# USB.net
KiCad netlist of a schematic drawn in Altium Designer
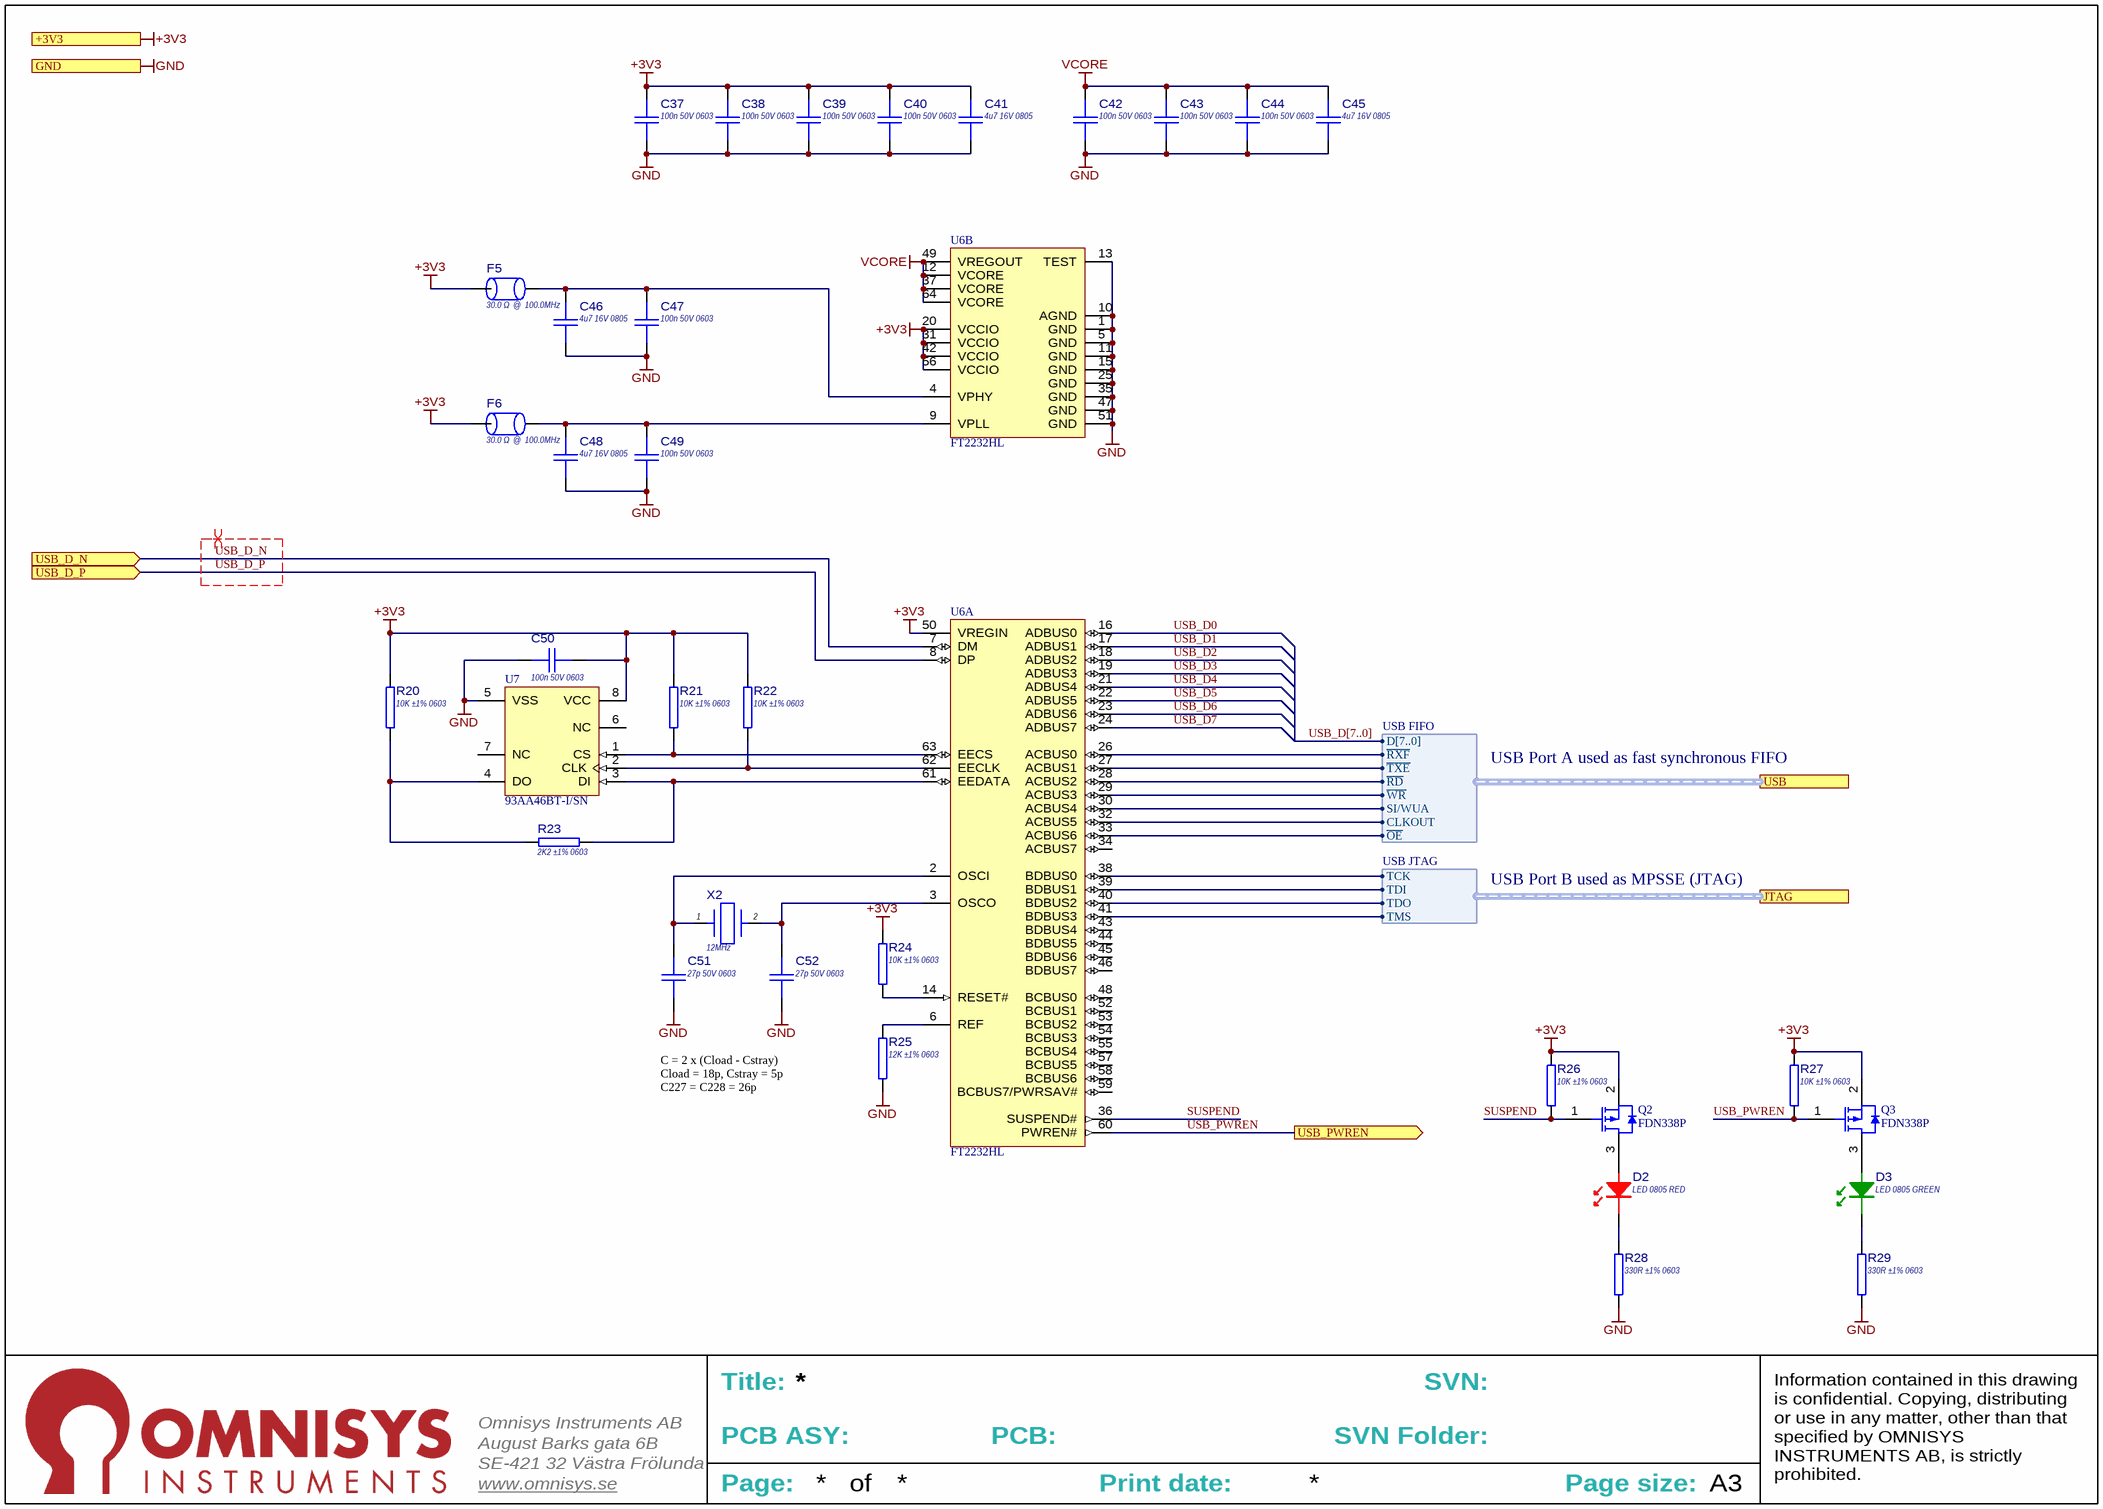
[diagram p0: USB.SchDoc]

(export (version "E")
  (design (tool "Eeschema 10.0.6"))
  (components
    (comp (ref "C37")
      (value "100n 50V 0603")
      (footprint "CAPC1608X90N")
      (description "100n 50V X7R ±10% 0603 (1608 metric)")
      (fields (field (name "PARTNUMBER") "GRM188R71H104KA93") (field (name "TOLERANCE") "±10%"))
      (libsource (lib "Omnisys Vault") (part "CAP-2PIN"))
    )
    (comp (ref "C38")
      (value "100n 50V 0603")
      (footprint "CAPC1608X90N")
      (description "100n 50V X7R ±10% 0603 (1608 metric)")
      (fields (field (name "PARTNUMBER") "GRM188R71H104KA93") (field (name "TOLERANCE") "±10%"))
      (libsource (lib "Omnisys Vault") (part "CAP-2PIN"))
    )
    (comp (ref "C39")
      (value "100n 50V 0603")
      (footprint "CAPC1608X90N")
      (description "100n 50V X7R ±10% 0603 (1608 metric)")
      (fields (field (name "PARTNUMBER") "GRM188R71H104KA93") (field (name "TOLERANCE") "±10%"))
      (libsource (lib "Omnisys Vault") (part "CAP-2PIN"))
    )
    (comp (ref "C40")
      (value "100n 50V 0603")
      (footprint "CAPC1608X90N")
      (description "100n 50V X7R ±10% 0603 (1608 metric)")
      (fields (field (name "PARTNUMBER") "GRM188R71H104KA93") (field (name "TOLERANCE") "±10%"))
      (libsource (lib "Omnisys Vault") (part "CAP-2PIN"))
    )
    (comp (ref "C41")
      (value "4u7 16V 0805")
      (footprint "CAPC2012X140N")
      (description "4u7 16V X7R ±10% 0805 (2012 metric)")
      (fields (field (name "PARTNUMBER") "GRM21BR71C475KA73") (field (name "TOLERANCE") "10%"))
      (libsource (lib "Omnisys Vault") (part "CAP-2PIN"))
    )
    (comp (ref "C42")
      (value "100n 50V 0603")
      (footprint "CAPC1608X90N")
      (description "100n 50V X7R ±10% 0603 (1608 metric)")
      (fields (field (name "PARTNUMBER") "GRM188R71H104KA93") (field (name "TOLERANCE") "±10%"))
      (libsource (lib "Omnisys Vault") (part "CAP-2PIN"))
    )
    (comp (ref "C43")
      (value "100n 50V 0603")
      (footprint "CAPC1608X90N")
      (description "100n 50V X7R ±10% 0603 (1608 metric)")
      (fields (field (name "PARTNUMBER") "GRM188R71H104KA93") (field (name "TOLERANCE") "±10%"))
      (libsource (lib "Omnisys Vault") (part "CAP-2PIN"))
    )
    (comp (ref "C44")
      (value "100n 50V 0603")
      (footprint "CAPC1608X90N")
      (description "100n 50V X7R ±10% 0603 (1608 metric)")
      (fields (field (name "PARTNUMBER") "GRM188R71H104KA93") (field (name "TOLERANCE") "±10%"))
      (libsource (lib "Omnisys Vault") (part "CAP-2PIN"))
    )
    (comp (ref "C45")
      (value "4u7 16V 0805")
      (footprint "CAPC2012X140N")
      (description "4u7 16V X7R ±10% 0805 (2012 metric)")
      (fields (field (name "PARTNUMBER") "GRM21BR71C475KA73") (field (name "TOLERANCE") "10%"))
      (libsource (lib "Omnisys Vault") (part "CAP-2PIN"))
    )
    (comp (ref "C46")
      (value "4u7 16V 0805")
      (footprint "CAPC2012X140N")
      (description "4u7 16V X7R ±10% 0805 (2012 metric)")
      (fields (field (name "PARTNUMBER") "GRM21BR71C475KA73") (field (name "TOLERANCE") "10%"))
      (libsource (lib "Omnisys Vault") (part "CAP-2PIN"))
    )
    (comp (ref "C47")
      (value "100n 50V 0603")
      (footprint "CAPC1608X90N")
      (description "100n 50V X7R ±10% 0603 (1608 metric)")
      (fields (field (name "PARTNUMBER") "GRM188R71H104KA93") (field (name "TOLERANCE") "±10%"))
      (libsource (lib "Omnisys Vault") (part "CAP-2PIN"))
    )
    (comp (ref "C48")
      (value "4u7 16V 0805")
      (footprint "CAPC2012X140N")
      (description "4u7 16V X7R ±10% 0805 (2012 metric)")
      (fields (field (name "PARTNUMBER") "GRM21BR71C475KA73") (field (name "TOLERANCE") "10%"))
      (libsource (lib "Omnisys Vault") (part "CAP-2PIN"))
    )
    (comp (ref "C49")
      (value "100n 50V 0603")
      (footprint "CAPC1608X90N")
      (description "100n 50V X7R ±10% 0603 (1608 metric)")
      (fields (field (name "PARTNUMBER") "GRM188R71H104KA93") (field (name "TOLERANCE") "±10%"))
      (libsource (lib "Omnisys Vault") (part "CAP-2PIN"))
    )
    (comp (ref "C50")
      (value "100n 50V 0603")
      (footprint "CAPC1608X90N")
      (description "100n 50V X7R ±10% 0603 (1608 metric)")
      (fields (field (name "PARTNUMBER") "GRM188R71H104KA93") (field (name "TOLERANCE") "±10%"))
      (libsource (lib "Omnisys Vault") (part "CAP-2PIN"))
    )
    (comp (ref "C51")
      (value "27p 50V 0603")
      (footprint "CAPC1608X90N")
      (description "27p 50V C0G ±5% 0603 (1608 metric)")
      (fields (field (name "PARTNUMBER") "GRM1885C1H270JA01") (field (name "TOLERANCE") "±5%"))
      (libsource (lib "Omnisys Vault") (part "CAP-2PIN"))
    )
    (comp (ref "C52")
      (value "27p 50V 0603")
      (footprint "CAPC1608X90N")
      (description "27p 50V C0G ±5% 0603 (1608 metric)")
      (fields (field (name "PARTNUMBER") "GRM1885C1H270JA01") (field (name "TOLERANCE") "±5%"))
      (libsource (lib "Omnisys Vault") (part "CAP-2PIN"))
    )
    (comp (ref "D2")
      (value "LED 0805 RED")
      (footprint "LED2012-RED")
      (libsource (lib "Omnisys Vault") (part "LED-2PIN-RED"))
    )
    (comp (ref "D3")
      (value "LED 0805 GREEN")
      (footprint "LED2012-GREEN")
      (libsource (lib "Omnisys Vault") (part "LED-2PIN-GREEN"))
    )
    (comp (ref "F5")
      (value "30.0 Ω  @  100.0MHz")
      (footprint "INDC2012X11N")
      (description "Ferrite bead, Würth Elektronik WE-CBF 2012 (0805), 74279206 ,  30.0 Ω  @  100.0MHz")
      (fields (field (name "PARTNUMBER") "74279206"))
      (libsource (lib "Omnisys Vault") (part "BEAD-2PIN"))
    )
    (comp (ref "F6")
      (value "30.0 Ω  @  100.0MHz")
      (footprint "INDC2012X11N")
      (description "Ferrite bead, Würth Elektronik WE-CBF 2012 (0805), 74279206 ,  30.0 Ω  @  100.0MHz")
      (fields (field (name "PARTNUMBER") "74279206"))
      (libsource (lib "Omnisys Vault") (part "BEAD-2PIN"))
    )
    (comp (ref "Q2")
      (value "FDN338P")
      (footprint "FAIR-SSOT3L-3_V")
      (fields (field (name "MANUFACTURER") "Fairchild Semiconductor"))
      (libsource (lib "Altium Content Vault") (part "PEMOS-GSD-3"))
    )
    (comp (ref "Q3")
      (value "FDN338P")
      (footprint "FAIR-SSOT3L-3_V")
      (fields (field (name "MANUFACTURER") "Fairchild Semiconductor"))
      (libsource (lib "Altium Content Vault") (part "PEMOS-GSD-3"))
    )
    (comp (ref "R20")
      (value "10K ±1% 0603")
      (footprint "RESC1608N")
      (description "10K ±1% ±100 ppm/˚C 0.10W 75V 0603 (1608 metric)")
      (fields (field (name "POWER") "100mW") (field (name "TOLERANCE") "1%"))
      (libsource (lib "Omnisys Vault") (part "RES-2PIN"))
    )
    (comp (ref "R21")
      (value "10K ±1% 0603")
      (footprint "RESC1608N")
      (description "10K ±1% ±100 ppm/˚C 0.10W 75V 0603 (1608 metric)")
      (fields (field (name "POWER") "100mW") (field (name "TOLERANCE") "1%"))
      (libsource (lib "Omnisys Vault") (part "RES-2PIN"))
    )
    (comp (ref "R22")
      (value "10K ±1% 0603")
      (footprint "RESC1608N")
      (description "10K ±1% ±100 ppm/˚C 0.10W 75V 0603 (1608 metric)")
      (fields (field (name "POWER") "100mW") (field (name "TOLERANCE") "1%"))
      (libsource (lib "Omnisys Vault") (part "RES-2PIN"))
    )
    (comp (ref "R23")
      (value "2K2 ±1% 0603")
      (footprint "RESC1608N")
      (description "2K2 ±1% ±100 ppm/˚C 0.10W 75V 0603 (1608 metric)")
      (fields (field (name "POWER") "100mW") (field (name "TOLERANCE") "1%"))
      (libsource (lib "Omnisys Vault") (part "RES-2PIN"))
    )
    (comp (ref "R24")
      (value "10K ±1% 0603")
      (footprint "RESC1608N")
      (description "10K ±1% ±100 ppm/˚C 0.10W 75V 0603 (1608 metric)")
      (fields (field (name "POWER") "100mW") (field (name "TOLERANCE") "1%"))
      (libsource (lib "Omnisys Vault") (part "RES-2PIN"))
    )
    (comp (ref "R25")
      (value "12K ±1% 0603")
      (footprint "RESC1608N")
      (description "12K ±1% ±100 ppm/˚C 0.10W 75V 0603 (1608 metric)")
      (fields (field (name "POWER") "100mW") (field (name "TOLERANCE") "1%"))
      (libsource (lib "Omnisys Vault") (part "RES-2PIN"))
    )
    (comp (ref "R26")
      (value "10K ±1% 0603")
      (footprint "RESC1608N")
      (description "10K ±1% ±100 ppm/˚C 0.10W 75V 0603 (1608 metric)")
      (fields (field (name "POWER") "100mW") (field (name "TOLERANCE") "1%"))
      (libsource (lib "Omnisys Vault") (part "RES-2PIN"))
    )
    (comp (ref "R27")
      (value "10K ±1% 0603")
      (footprint "RESC1608N")
      (description "10K ±1% ±100 ppm/˚C 0.10W 75V 0603 (1608 metric)")
      (fields (field (name "POWER") "100mW") (field (name "TOLERANCE") "1%"))
      (libsource (lib "Omnisys Vault") (part "RES-2PIN"))
    )
    (comp (ref "R28")
      (value "330R ±1% 0603")
      (footprint "RESC1608N")
      (description "330R ±1% ±100 ppm/˚C 0.10W 75V 0603 (1608 metric)")
      (fields (field (name "POWER") "100mW") (field (name "TOLERANCE") "1%"))
      (libsource (lib "Omnisys Vault") (part "RES-2PIN"))
    )
    (comp (ref "R29")
      (value "330R ±1% 0603")
      (footprint "RESC1608N")
      (description "330R ±1% ±100 ppm/˚C 0.10W 75V 0603 (1608 metric)")
      (fields (field (name "POWER") "100mW") (field (name "TOLERANCE") "1%"))
      (libsource (lib "Omnisys Vault") (part "RES-2PIN"))
    )
    (comp (ref "U6")
      (value "FT2232HL")
      (footprint "FTDI-LQFP-64_L")
      (fields (field (name "MANUFACTURER") "FTDI"))
      (libsource (lib "Altium Content Vault") (part "FTDI-FT2232HL-LQFP-64"))
    )
    (comp (ref "U7")
      (value "93AA46BT-I/SN")
      (footprint "SOIC-SN8_L")
      (libsource (lib "Altium Content Vault") (part "MEM-SEEPROM-93AA46B-P-8"))
    )
    (comp (ref "X2")
      (value "12MHz")
      (footprint "XTAL_5x3.2MM")
      (description "12MHz 5 x 3.2 mm SMD GLASS CRYSTAL, 7A-12.000MAAJ-T")
      (fields (field (name "PARTNUMBER") "7A-12.000MAAJ-T"))
      (libsource (lib "Omnisys Vault") (part "XTAL-2PIN"))
    )
  )
  (nets
    (net (code "4") (name "+3V3") (class "Default")
      (node (ref "C37") (pin "1") (pinfunction "1_1") (pintype "passive"))
      (node (ref "C38") (pin "1") (pinfunction "1_1") (pintype "passive"))
      (node (ref "C39") (pin "1") (pinfunction "1_1") (pintype "passive"))
      (node (ref "C40") (pin "1") (pinfunction "1_1") (pintype "passive"))
      (node (ref "C41") (pin "2") (pinfunction "2_2") (pintype "passive"))
      (node (ref "C50") (pin "2") (pinfunction "2_2") (pintype "passive"))
      (node (ref "F5") (pin "1") (pinfunction "1_1") (pintype "passive"))
      (node (ref "F6") (pin "1") (pinfunction "1_1") (pintype "passive"))
      (node (ref "Q2") (pin "2") (pinfunction "SOURCE_2") (pintype "passive"))
      (node (ref "Q3") (pin "2") (pinfunction "SOURCE_2") (pintype "passive"))
      (node (ref "R20") (pin "2") (pinfunction "2_2") (pintype "passive"))
      (node (ref "R21") (pin "2") (pinfunction "2_2") (pintype "passive"))
      (node (ref "R22") (pin "2") (pinfunction "2_2") (pintype "passive"))
      (node (ref "R24") (pin "1") (pinfunction "1_1") (pintype "passive"))
      (node (ref "R26") (pin "2") (pinfunction "2_2") (pintype "passive"))
      (node (ref "R27") (pin "2") (pinfunction "2_2") (pintype "passive"))
      (node (ref "U6") (pin "20") (pinfunction "VCCIO_20") (pintype "power_in"))
      (node (ref "U6") (pin "31") (pinfunction "VCCIO_31") (pintype "power_in"))
      (node (ref "U6") (pin "42") (pinfunction "VCCIO_42") (pintype "power_in"))
      (node (ref "U6") (pin "50") (pinfunction "VREGIN_50") (pintype "power_in"))
      (node (ref "U6") (pin "56") (pinfunction "VCCIO_56") (pintype "power_in"))
      (node (ref "U7") (pin "8") (pinfunction "VCC_8") (pintype "power_in"))
    )
    (net (code "5") (name "/CLKOUT") (class "Default")
      (node (ref "U6") (pin "32") (pinfunction "ACBUS5_32") (pintype "bidirectional"))
    )
    (net (code "6") (name "/SI{slash}WUA") (class "Default")
      (node (ref "U6") (pin "30") (pinfunction "ACBUS4_30") (pintype "bidirectional"))
    )
    (net (code "7") (name "/SUSPEND") (class "Default")
      (node (ref "Q2") (pin "1") (pinfunction "GATE_1") (pintype "passive"))
      (node (ref "R26") (pin "1") (pinfunction "1_1") (pintype "passive"))
      (node (ref "U6") (pin "36") (pinfunction "SUSPEND#_36") (pintype "output"))
    )
    (net (code "8") (name "/TCK") (class "Default")
      (node (ref "U6") (pin "38") (pinfunction "BDBUS0_38") (pintype "bidirectional"))
    )
    (net (code "9") (name "/TDI") (class "Default")
      (node (ref "U6") (pin "39") (pinfunction "BDBUS1_39") (pintype "bidirectional"))
    )
    (net (code "10") (name "/TDO") (class "Default")
      (node (ref "U6") (pin "40") (pinfunction "BDBUS2_40") (pintype "bidirectional"))
    )
    (net (code "11") (name "/TMS") (class "Default")
      (node (ref "U6") (pin "41") (pinfunction "BDBUS3_41") (pintype "bidirectional"))
    )
    (net (code "12") (name "/USB_D0") (class "Default")
      (node (ref "U6") (pin "16") (pinfunction "ADBUS0_16") (pintype "bidirectional"))
    )
    (net (code "13") (name "/USB_D1") (class "Default")
      (node (ref "U6") (pin "17") (pinfunction "ADBUS1_17") (pintype "bidirectional"))
    )
    (net (code "14") (name "/USB_D2") (class "Default")
      (node (ref "U6") (pin "18") (pinfunction "ADBUS2_18") (pintype "bidirectional"))
    )
    (net (code "15") (name "/USB_D3") (class "Default")
      (node (ref "U6") (pin "19") (pinfunction "ADBUS3_19") (pintype "bidirectional"))
    )
    (net (code "16") (name "/USB_D4") (class "Default")
      (node (ref "U6") (pin "21") (pinfunction "ADBUS4_21") (pintype "bidirectional"))
    )
    (net (code "17") (name "/USB_D5") (class "Default")
      (node (ref "U6") (pin "22") (pinfunction "ADBUS5_22") (pintype "bidirectional"))
    )
    (net (code "18") (name "/USB_D6") (class "Default")
      (node (ref "U6") (pin "23") (pinfunction "ADBUS6_23") (pintype "bidirectional"))
    )
    (net (code "19") (name "/USB_D7") (class "Default")
      (node (ref "U6") (pin "24") (pinfunction "ADBUS7_24") (pintype "bidirectional"))
    )
    (net (code "21") (name "/USB_D_N") (class "Default")
      (node (ref "U6") (pin "7") (pinfunction "DM_7") (pintype "bidirectional"))
    )
    (net (code "22") (name "/USB_D_P") (class "Default")
      (node (ref "U6") (pin "8") (pinfunction "DP_8") (pintype "bidirectional"))
    )
    (net (code "23") (name "/USB_PWREN") (class "Default")
      (node (ref "Q3") (pin "1") (pinfunction "GATE_1") (pintype "passive"))
      (node (ref "R27") (pin "1") (pinfunction "1_1") (pintype "passive"))
      (node (ref "U6") (pin "60") (pinfunction "PWREN#_60") (pintype "output"))
    )
    (net (code "26") (name "/~{OE}") (class "Default")
      (node (ref "U6") (pin "33") (pinfunction "ACBUS6_33") (pintype "bidirectional"))
    )
    (net (code "27") (name "/~{RD}") (class "Default")
      (node (ref "U6") (pin "28") (pinfunction "ACBUS2_28") (pintype "bidirectional"))
    )
    (net (code "28") (name "/~{RXF}") (class "Default")
      (node (ref "U6") (pin "26") (pinfunction "ACBUS0_26") (pintype "bidirectional"))
    )
    (net (code "29") (name "/~{TXE}") (class "Default")
      (node (ref "U6") (pin "27") (pinfunction "ACBUS1_27") (pintype "bidirectional"))
    )
    (net (code "30") (name "/~{WR}") (class "Default")
      (node (ref "U6") (pin "29") (pinfunction "ACBUS3_29") (pintype "bidirectional"))
    )
    (net (code "31") (name "GND") (class "Default")
      (node (ref "C37") (pin "2") (pinfunction "2_2") (pintype "passive"))
      (node (ref "C38") (pin "2") (pinfunction "2_2") (pintype "passive"))
      (node (ref "C39") (pin "2") (pinfunction "2_2") (pintype "passive"))
      (node (ref "C40") (pin "2") (pinfunction "2_2") (pintype "passive"))
      (node (ref "C41") (pin "1") (pinfunction "1_1") (pintype "passive"))
      (node (ref "C42") (pin "2") (pinfunction "2_2") (pintype "passive"))
      (node (ref "C43") (pin "2") (pinfunction "2_2") (pintype "passive"))
      (node (ref "C44") (pin "2") (pinfunction "2_2") (pintype "passive"))
      (node (ref "C45") (pin "1") (pinfunction "1_1") (pintype "passive"))
      (node (ref "C46") (pin "1") (pinfunction "1_1") (pintype "passive"))
      (node (ref "C47") (pin "1") (pinfunction "1_1") (pintype "passive"))
      (node (ref "C48") (pin "1") (pinfunction "1_1") (pintype "passive"))
      (node (ref "C49") (pin "1") (pinfunction "1_1") (pintype "passive"))
      (node (ref "C50") (pin "1") (pinfunction "1_1") (pintype "passive"))
      (node (ref "C51") (pin "1") (pinfunction "1_1") (pintype "passive"))
      (node (ref "C52") (pin "1") (pinfunction "1_1") (pintype "passive"))
      (node (ref "R25") (pin "1") (pinfunction "1_1") (pintype "passive"))
      (node (ref "R28") (pin "1") (pinfunction "1_1") (pintype "passive"))
      (node (ref "R29") (pin "1") (pinfunction "1_1") (pintype "passive"))
      (node (ref "U6") (pin "1") (pinfunction "GND_1") (pintype "power_in"))
      (node (ref "U6") (pin "10") (pinfunction "AGND_10") (pintype "power_in"))
      (node (ref "U6") (pin "11") (pinfunction "GND_11") (pintype "power_in"))
      (node (ref "U6") (pin "13") (pinfunction "TEST_13") (pintype "passive"))
      (node (ref "U6") (pin "15") (pinfunction "GND_15") (pintype "power_in"))
      (node (ref "U6") (pin "25") (pinfunction "GND_25") (pintype "power_in"))
      (node (ref "U6") (pin "35") (pinfunction "GND_35") (pintype "power_in"))
      (node (ref "U6") (pin "47") (pinfunction "GND_47") (pintype "power_in"))
      (node (ref "U6") (pin "5") (pinfunction "GND_5") (pintype "power_in"))
      (node (ref "U6") (pin "51") (pinfunction "GND_51") (pintype "power_in"))
      (node (ref "U7") (pin "5") (pinfunction "VSS_5") (pintype "power_in"))
    )
    (net (code "32") (name "Net-(D2-Pad1)") (class "Default")
      (node (ref "D2") (pin "1") (pintype "passive"))
      (node (ref "R28") (pin "2") (pinfunction "2_2") (pintype "passive"))
    )
    (net (code "33") (name "Net-(D3-Pad1)") (class "Default")
      (node (ref "D3") (pin "1") (pintype "passive"))
      (node (ref "R29") (pin "2") (pinfunction "2_2") (pintype "passive"))
    )
    (net (code "34") (name "Net-(Q2-DRAIN)") (class "Default")
      (node (ref "D2") (pin "2") (pintype "passive"))
      (node (ref "Q2") (pin "3") (pinfunction "DRAIN_3") (pintype "passive"))
    )
    (net (code "35") (name "Net-(Q3-DRAIN)") (class "Default")
      (node (ref "D3") (pin "2") (pintype "passive"))
      (node (ref "Q3") (pin "3") (pinfunction "DRAIN_3") (pintype "passive"))
    )
    (net (code "36") (name "Net-(U6A-EECLK)") (class "Default")
      (node (ref "R22") (pin "1") (pinfunction "1_1") (pintype "passive"))
      (node (ref "U6") (pin "62") (pinfunction "EECLK_62") (pintype "tri_state"))
      (node (ref "U7") (pin "2") (pinfunction "CLK_2") (pintype "input"))
    )
    (net (code "37") (name "Net-(U6A-EECS)") (class "Default")
      (node (ref "R21") (pin "1") (pinfunction "1_1") (pintype "passive"))
      (node (ref "U6") (pin "63") (pinfunction "EECS_63") (pintype "bidirectional"))
      (node (ref "U7") (pin "1") (pinfunction "CS_1") (pintype "input"))
    )
    (net (code "38") (name "Net-(U6A-EEDATA)") (class "Default")
      (node (ref "R23") (pin "2") (pinfunction "2_2") (pintype "passive"))
      (node (ref "U6") (pin "61") (pinfunction "EEDATA_61") (pintype "bidirectional"))
      (node (ref "U7") (pin "3") (pinfunction "DI_3") (pintype "input"))
    )
    (net (code "39") (name "Net-(U6A-OSCI)") (class "Default")
      (node (ref "C51") (pin "2") (pinfunction "2_2") (pintype "passive"))
      (node (ref "U6") (pin "2") (pinfunction "OSCI_2") (pintype "passive"))
      (node (ref "X2") (pin "1") (pinfunction "1_1") (pintype "passive"))
    )
    (net (code "40") (name "Net-(U6A-OSCO)") (class "Default")
      (node (ref "C52") (pin "2") (pinfunction "2_2") (pintype "passive"))
      (node (ref "U6") (pin "3") (pinfunction "OSCO_3") (pintype "passive"))
      (node (ref "X2") (pin "2") (pinfunction "2_2") (pintype "passive"))
    )
    (net (code "41") (name "Net-(U6A-REF)") (class "Default")
      (node (ref "R25") (pin "2") (pinfunction "2_2") (pintype "passive"))
      (node (ref "U6") (pin "6") (pinfunction "REF_6") (pintype "passive"))
    )
    (net (code "42") (name "Net-(U6A-RESET#)") (class "Default")
      (node (ref "R24") (pin "2") (pinfunction "2_2") (pintype "passive"))
      (node (ref "U6") (pin "14") (pinfunction "RESET#_14") (pintype "input"))
    )
    (net (code "43") (name "Net-(U6B-VPHY)") (class "Default")
      (node (ref "C46") (pin "2") (pinfunction "2_2") (pintype "passive"))
      (node (ref "C47") (pin "2") (pinfunction "2_2") (pintype "passive"))
      (node (ref "F5") (pin "2") (pinfunction "2_2") (pintype "passive"))
      (node (ref "U6") (pin "4") (pinfunction "VPHY_4") (pintype "power_in"))
    )
    (net (code "44") (name "Net-(U6B-VPLL)") (class "Default")
      (node (ref "C48") (pin "2") (pinfunction "2_2") (pintype "passive"))
      (node (ref "C49") (pin "2") (pinfunction "2_2") (pintype "passive"))
      (node (ref "F6") (pin "2") (pinfunction "2_2") (pintype "passive"))
      (node (ref "U6") (pin "9") (pinfunction "VPLL_9") (pintype "power_in"))
    )
    (net (code "45") (name "Net-(U7-DO)") (class "Default")
      (node (ref "R20") (pin "1") (pinfunction "1_1") (pintype "passive"))
      (node (ref "R23") (pin "1") (pinfunction "1_1") (pintype "passive"))
      (node (ref "U7") (pin "4") (pinfunction "DO_4") (pintype "tri_state"))
    )
    (net (code "46") (name "VCORE") (class "Default")
      (node (ref "C42") (pin "1") (pinfunction "1_1") (pintype "passive"))
      (node (ref "C43") (pin "1") (pinfunction "1_1") (pintype "passive"))
      (node (ref "C44") (pin "1") (pinfunction "1_1") (pintype "passive"))
      (node (ref "C45") (pin "2") (pinfunction "2_2") (pintype "passive"))
      (node (ref "U6") (pin "12") (pinfunction "VCORE_12") (pintype "power_in"))
      (node (ref "U6") (pin "37") (pinfunction "VCORE_37") (pintype "power_in"))
      (node (ref "U6") (pin "49") (pinfunction "VREGOUT_49") (pintype "power_in"))
      (node (ref "U6") (pin "64") (pinfunction "VCORE_64") (pintype "power_in"))
    )
    (net (code "47") (name "unconnected-(U6A-ACBUS7-Pad34)") (class "Default")
      (node (ref "U6") (pin "34") (pinfunction "ACBUS7_34") (pintype "bidirectional"))
    )
    (net (code "48") (name "unconnected-(U6A-BCBUS0-Pad48)") (class "Default")
      (node (ref "U6") (pin "48") (pinfunction "BCBUS0_48") (pintype "bidirectional"))
    )
    (net (code "49") (name "unconnected-(U6A-BCBUS1-Pad52)") (class "Default")
      (node (ref "U6") (pin "52") (pinfunction "BCBUS1_52") (pintype "bidirectional"))
    )
    (net (code "50") (name "unconnected-(U6A-BCBUS2-Pad53)") (class "Default")
      (node (ref "U6") (pin "53") (pinfunction "BCBUS2_53") (pintype "bidirectional"))
    )
    (net (code "51") (name "unconnected-(U6A-BCBUS3-Pad54)") (class "Default")
      (node (ref "U6") (pin "54") (pinfunction "BCBUS3_54") (pintype "bidirectional"))
    )
    (net (code "52") (name "unconnected-(U6A-BCBUS4-Pad55)") (class "Default")
      (node (ref "U6") (pin "55") (pinfunction "BCBUS4_55") (pintype "bidirectional"))
    )
    (net (code "53") (name "unconnected-(U6A-BCBUS5-Pad57)") (class "Default")
      (node (ref "U6") (pin "57") (pinfunction "BCBUS5_57") (pintype "bidirectional"))
    )
    (net (code "54") (name "unconnected-(U6A-BCBUS6-Pad58)") (class "Default")
      (node (ref "U6") (pin "58") (pinfunction "BCBUS6_58") (pintype "bidirectional"))
    )
    (net (code "55") (name "unconnected-(U6A-BCBUS7{slash}PWRSAV#-Pad59)") (class "Default")
      (node (ref "U6") (pin "59") (pinfunction "BCBUS7/PWRSAV#_59") (pintype "bidirectional"))
    )
    (net (code "56") (name "unconnected-(U6A-BDBUS4-Pad43)") (class "Default")
      (node (ref "U6") (pin "43") (pinfunction "BDBUS4_43") (pintype "bidirectional"))
    )
    (net (code "57") (name "unconnected-(U6A-BDBUS5-Pad44)") (class "Default")
      (node (ref "U6") (pin "44") (pinfunction "BDBUS5_44") (pintype "bidirectional"))
    )
    (net (code "58") (name "unconnected-(U6A-BDBUS6-Pad45)") (class "Default")
      (node (ref "U6") (pin "45") (pinfunction "BDBUS6_45") (pintype "bidirectional"))
    )
    (net (code "59") (name "unconnected-(U6A-BDBUS7-Pad46)") (class "Default")
      (node (ref "U6") (pin "46") (pinfunction "BDBUS7_46") (pintype "bidirectional"))
    )
    (net (code "60") (name "unconnected-(U7-NC-Pad6)") (class "Default")
      (node (ref "U7") (pin "6") (pinfunction "NC_6") (pintype "passive"))
    )
    (net (code "61") (name "unconnected-(U7-NC-Pad7)") (class "Default")
      (node (ref "U7") (pin "7") (pinfunction "NC_7") (pintype "passive"))
    )
  )
)
